# K22.net
KiCad netlist of a schematic drawn in Altium Designer
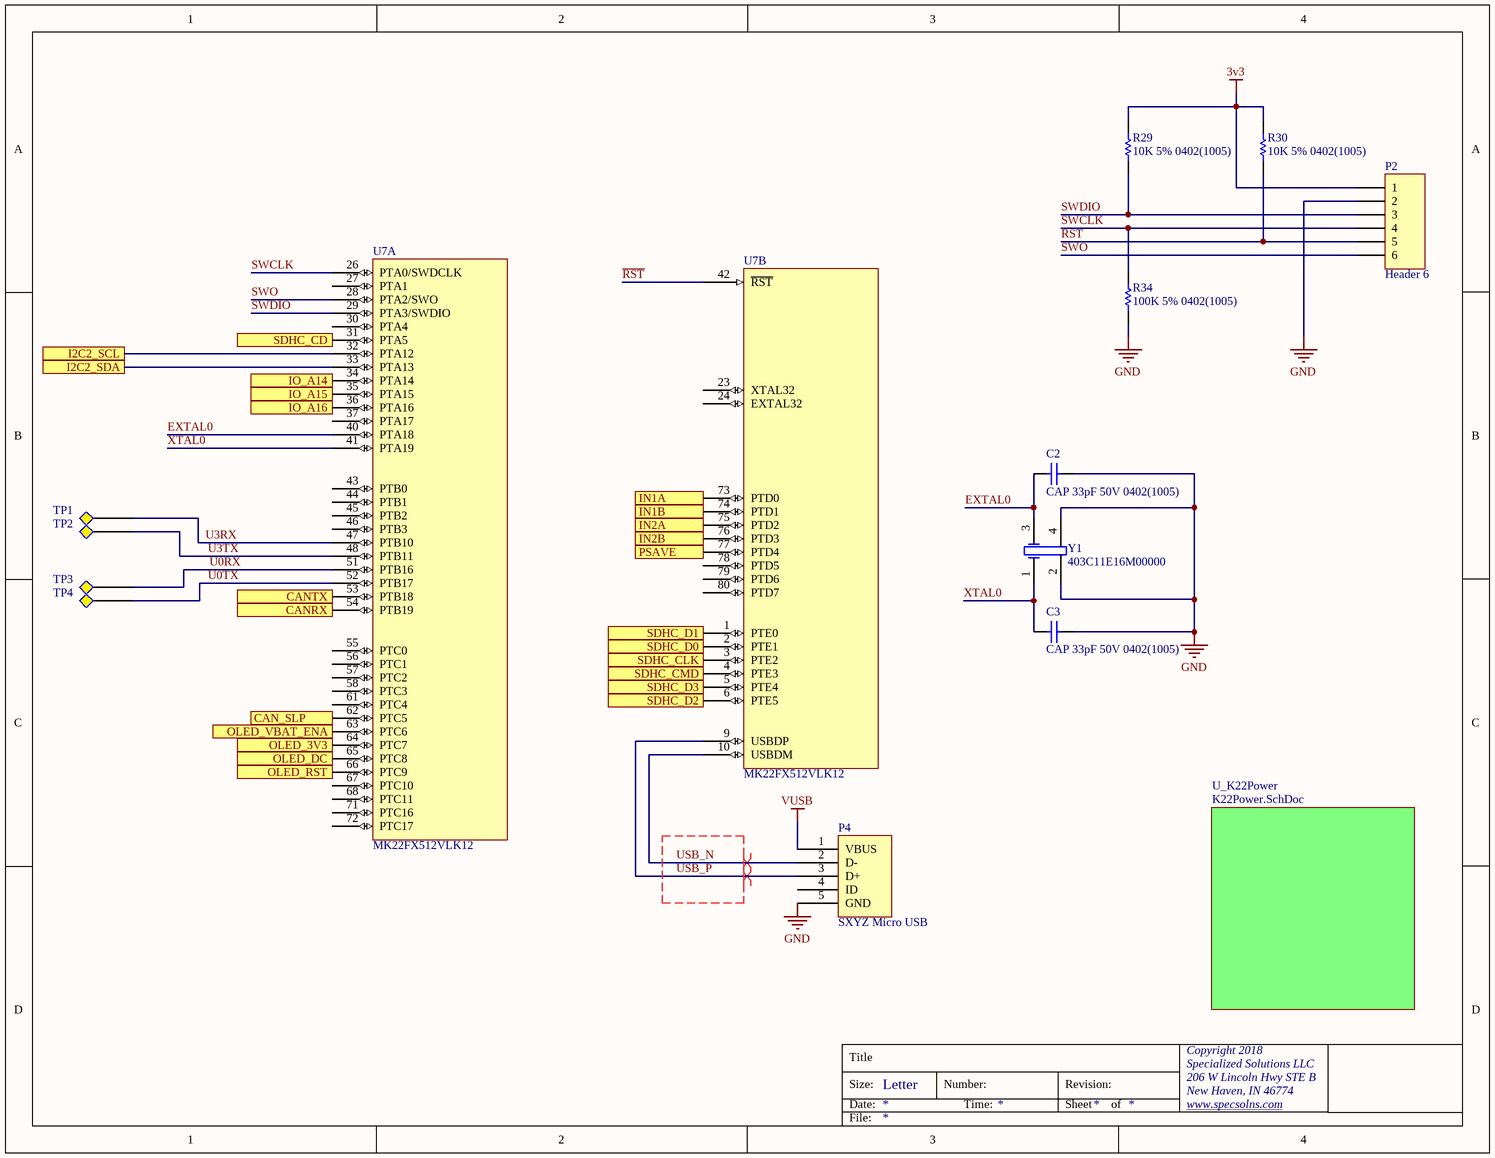
[diagram p0: K22.SchDoc]

(export (version "E")
  (design (tool "Eeschema 10.0.6"))
  (components
    (comp (ref "C2")
      (value "CAP 33pF 50V 0402(1005)")
      (footprint "CAPC0402(1005)60_N")
      (description "CAP 33pF 50V ±5% 0402 (1005 Metric) Thickness 0.6mm SMD")
      (fields (field (name "TOLERANCE") "Â±5%"))
      (libsource (lib "Altium Content Vault") (part "CAP"))
    )
    (comp (ref "C3")
      (value "CAP 33pF 50V 0402(1005)")
      (footprint "CAPC0402(1005)60_N")
      (description "CAP 33pF 50V ±5% 0402 (1005 Metric) Thickness 0.6mm SMD")
      (fields (field (name "TOLERANCE") "Â±5%"))
      (libsource (lib "Altium Content Vault") (part "CAP"))
    )
    (comp (ref "P2")
      (value "Header 6")
      (footprint "Parts:HDR1X6")
      (description "Header, 6-Pin")
      (fields (field (name "PUBLISHER") "Altium Limited"))
      (libsource (lib "Miscellaneous Connectors") (part "Header 6"))
    )
    (comp (ref "P4")
      (value "SXYZ Micro USB")
      (footprint "SXYZ Micro USB")
      (description "Micro USB Connector")
      (libsource (lib "Parts") (part "SXYZ MicroUSB"))
    )
    (comp (ref "R29")
      (value "10K 5% 0402(1005)")
      (footprint "RESC0402(1005)_N")
      (description "10K 0.063W 5% 0402 (1005 Metric)  SMD")
      (fields (field (name "TOLERANCE") "5 %") (field (name "POWER") "0.063 W"))
      (libsource (lib "Altium Content Vault") (part "RES"))
    )
    (comp (ref "R30")
      (value "10K 5% 0402(1005)")
      (footprint "RESC0402(1005)_N")
      (description "10K 0.063W 5% 0402 (1005 Metric)  SMD")
      (fields (field (name "TOLERANCE") "5 %") (field (name "POWER") "0.063 W"))
      (libsource (lib "Altium Content Vault") (part "RES"))
    )
    (comp (ref "R34")
      (value "100K 5% 0402(1005)")
      (footprint "RESC0402(1005)_L")
      (description "100K 0.063W 5% 0402 (1005 Metric)  SMD")
      (fields (field (name "POWER") "0.063 W") (field (name "TOLERANCE") "5 %"))
      (libsource (lib "Altium Content Vault") (part "RES"))
    )
    (comp (ref "TP1") (value "Test Point") (footprint "TP") (libsource (lib "parts") (part "TP")))
    (comp (ref "TP2") (value "Test Point") (footprint "TP") (libsource (lib "parts") (part "TP")))
    (comp (ref "TP3") (value "Test Point") (footprint "TP") (libsource (lib "parts") (part "TP")))
    (comp (ref "TP4") (value "Test Point") (footprint "TP") (libsource (lib "parts") (part "TP")))
    (comp (ref "U7")
      (value "MK22FX512VLK12")
      (footprint "TSQFP50P1400X1400X160-80N")
      (libsource (lib "parts") (part "MK22FX512VLK12"))
    )
    (comp (ref "Y1")
      (value "403C11E16M00000")
      (footprint "DFN155P250X80-4N")
      (description "CRYSTAL 16.0000MHZ 20PF SMD 3.20x2.50")
      (fields (field (name "PUBLISHER") "Altium Limited"))
      (libsource (lib "parts") (part "403C11E16M00000"))
    )
  )
  (nets
    (net (code "1") (name "/CANRX") (class "Default")
      (node (ref "U7") (pin "54") (pinfunction "PTB19_54") (pintype "bidirectional"))
    )
    (net (code "2") (name "/CANTX") (class "Default")
      (node (ref "U7") (pin "53") (pinfunction "PTB18_53") (pintype "bidirectional"))
    )
    (net (code "3") (name "/CAN_SLP") (class "Default")
      (node (ref "U7") (pin "62") (pinfunction "PTC5_62") (pintype "bidirectional"))
    )
    (net (code "4") (name "/EXTAL0") (class "Default")
      (node (ref "C2") (pin "1") (pinfunction "1_1") (pintype "passive"))
      (node (ref "U7") (pin "40") (pinfunction "PTA18_40") (pintype "bidirectional"))
      (node (ref "Y1") (pin "3") (pinfunction "OSC2_3") (pintype "passive"))
    )
    (net (code "5") (name "/I2C2_SCL") (class "Default")
      (node (ref "U7") (pin "32") (pinfunction "PTA12_32") (pintype "bidirectional"))
    )
    (net (code "6") (name "/I2C2_SDA") (class "Default")
      (node (ref "U7") (pin "33") (pinfunction "PTA13_33") (pintype "bidirectional"))
    )
    (net (code "7") (name "/IN1A") (class "Default")
      (node (ref "U7") (pin "73") (pinfunction "PTD0_73") (pintype "bidirectional"))
    )
    (net (code "8") (name "/IN1B") (class "Default")
      (node (ref "U7") (pin "74") (pinfunction "PTD1_74") (pintype "bidirectional"))
    )
    (net (code "9") (name "/IN2A") (class "Default")
      (node (ref "U7") (pin "75") (pinfunction "PTD2_75") (pintype "bidirectional"))
    )
    (net (code "10") (name "/IN2B") (class "Default")
      (node (ref "U7") (pin "76") (pinfunction "PTD3_76") (pintype "bidirectional"))
    )
    (net (code "11") (name "/IO_A14") (class "Default")
      (node (ref "U7") (pin "34") (pinfunction "PTA14_34") (pintype "bidirectional"))
    )
    (net (code "12") (name "/IO_A15") (class "Default")
      (node (ref "U7") (pin "35") (pinfunction "PTA15_35") (pintype "bidirectional"))
    )
    (net (code "13") (name "/IO_A16") (class "Default")
      (node (ref "U7") (pin "36") (pinfunction "PTA16_36") (pintype "bidirectional"))
    )
    (net (code "14") (name "/OLED_3V3") (class "Default")
      (node (ref "U7") (pin "64") (pinfunction "PTC7_64") (pintype "bidirectional"))
    )
    (net (code "15") (name "/OLED_DC") (class "Default")
      (node (ref "U7") (pin "65") (pinfunction "PTC8_65") (pintype "bidirectional"))
    )
    (net (code "16") (name "/OLED_RST") (class "Default")
      (node (ref "U7") (pin "66") (pinfunction "PTC9_66") (pintype "bidirectional"))
    )
    (net (code "17") (name "/OLED_VBAT_ENA") (class "Default")
      (node (ref "U7") (pin "63") (pinfunction "PTC6_63") (pintype "bidirectional"))
    )
    (net (code "18") (name "/PSAVE") (class "Default")
      (node (ref "U7") (pin "77") (pinfunction "PTD4_77") (pintype "bidirectional"))
    )
    (net (code "19") (name "/RST") (class "Default")
      (node (ref "P2") (pin "5") (pinfunction "5_5") (pintype "passive"))
      (node (ref "R30") (pin "1") (pinfunction "1_1") (pintype "passive"))
      (node (ref "U7") (pin "42") (pinfunction "RST_42") (pintype "input"))
    )
    (net (code "20") (name "/SDHC_CD") (class "Default")
      (node (ref "U7") (pin "31") (pinfunction "PTA5_31") (pintype "bidirectional"))
    )
    (net (code "21") (name "/SDHC_CLK") (class "Default")
      (node (ref "U7") (pin "3") (pinfunction "PTE2_3") (pintype "bidirectional"))
    )
    (net (code "22") (name "/SDHC_CMD") (class "Default")
      (node (ref "U7") (pin "4") (pinfunction "PTE3_4") (pintype "bidirectional"))
    )
    (net (code "23") (name "/SDHC_D0") (class "Default")
      (node (ref "U7") (pin "2") (pinfunction "PTE1_2") (pintype "bidirectional"))
    )
    (net (code "24") (name "/SDHC_D1") (class "Default")
      (node (ref "U7") (pin "1") (pinfunction "PTE0_1") (pintype "bidirectional"))
    )
    (net (code "25") (name "/SDHC_D2") (class "Default")
      (node (ref "U7") (pin "6") (pinfunction "PTE5_6") (pintype "bidirectional"))
    )
    (net (code "26") (name "/SDHC_D3") (class "Default")
      (node (ref "U7") (pin "5") (pinfunction "PTE4_5") (pintype "bidirectional"))
    )
    (net (code "27") (name "/SWCLK") (class "Default")
      (node (ref "P2") (pin "4") (pinfunction "4_4") (pintype "passive"))
      (node (ref "R34") (pin "2") (pinfunction "2_2") (pintype "passive"))
      (node (ref "U7") (pin "26") (pinfunction "PTA0/SWDCLK_26") (pintype "bidirectional"))
    )
    (net (code "28") (name "/SWDIO") (class "Default")
      (node (ref "P2") (pin "3") (pinfunction "3_3") (pintype "passive"))
      (node (ref "R29") (pin "1") (pinfunction "1_1") (pintype "passive"))
      (node (ref "U7") (pin "29") (pinfunction "PTA3/SWDIO_29") (pintype "bidirectional"))
    )
    (net (code "29") (name "/SWO") (class "Default")
      (node (ref "P2") (pin "6") (pinfunction "6_6") (pintype "passive"))
      (node (ref "U7") (pin "28") (pinfunction "PTA2/SWO_28") (pintype "bidirectional"))
    )
    (net (code "30") (name "/U0RX") (class "Default")
      (node (ref "TP3") (pin "1") (pinfunction "1_1") (pintype "passive"))
      (node (ref "U7") (pin "51") (pinfunction "PTB16_51") (pintype "bidirectional"))
    )
    (net (code "31") (name "/U0TX") (class "Default")
      (node (ref "TP4") (pin "1") (pinfunction "1_1") (pintype "passive"))
      (node (ref "U7") (pin "52") (pinfunction "PTB17_52") (pintype "bidirectional"))
    )
    (net (code "32") (name "/U3RX") (class "Default")
      (node (ref "TP1") (pin "1") (pinfunction "1_1") (pintype "passive"))
      (node (ref "U7") (pin "47") (pinfunction "PTB10_47") (pintype "bidirectional"))
    )
    (net (code "33") (name "/U3TX") (class "Default")
      (node (ref "TP2") (pin "1") (pinfunction "1_1") (pintype "passive"))
      (node (ref "U7") (pin "48") (pinfunction "PTB11_48") (pintype "bidirectional"))
    )
    (net (code "34") (name "/USB_N") (class "Default")
      (node (ref "P4") (pin "2") (pinfunction "D-_2") (pintype "passive"))
      (node (ref "U7") (pin "10") (pinfunction "USBDM_10") (pintype "bidirectional"))
    )
    (net (code "35") (name "/USB_P") (class "Default")
      (node (ref "P4") (pin "3") (pinfunction "D+_3") (pintype "passive"))
      (node (ref "U7") (pin "9") (pinfunction "USBDP_9") (pintype "bidirectional"))
    )
    (net (code "36") (name "/XTAL0") (class "Default")
      (node (ref "C3") (pin "1") (pinfunction "1_1") (pintype "passive"))
      (node (ref "U7") (pin "41") (pinfunction "PTA19_41") (pintype "bidirectional"))
      (node (ref "Y1") (pin "1") (pinfunction "OSC1_1") (pintype "passive"))
    )
    (net (code "37") (name "3v3") (class "Default")
      (node (ref "P2") (pin "1") (pinfunction "1_1") (pintype "passive"))
      (node (ref "R29") (pin "2") (pinfunction "2_2") (pintype "passive"))
      (node (ref "R30") (pin "2") (pinfunction "2_2") (pintype "passive"))
    )
    (net (code "38") (name "GND") (class "Default")
      (node (ref "C2") (pin "2") (pinfunction "2_2") (pintype "passive"))
      (node (ref "C3") (pin "2") (pinfunction "2_2") (pintype "passive"))
      (node (ref "P2") (pin "2") (pinfunction "2_2") (pintype "passive"))
      (node (ref "P4") (pin "5") (pinfunction "GND_5") (pintype "passive"))
      (node (ref "R34") (pin "1") (pinfunction "1_1") (pintype "passive"))
      (node (ref "Y1") (pin "2") (pinfunction "GND_2") (pintype "passive"))
      (node (ref "Y1") (pin "4") (pinfunction "GND_4") (pintype "passive"))
    )
    (net (code "39") (name "VUSB") (class "Default")
      (node (ref "P4") (pin "1") (pinfunction "VBUS_1") (pintype "passive"))
    )
    (net (code "40") (name "unconnected-(P4-ID-Pad4)") (class "Default")
      (node (ref "P4") (pin "4") (pinfunction "ID_4") (pintype "passive"))
    )
    (net (code "41") (name "unconnected-(U7A-PTA1-Pad27)") (class "Default")
      (node (ref "U7") (pin "27") (pinfunction "PTA1_27") (pintype "bidirectional"))
    )
    (net (code "42") (name "unconnected-(U7A-PTA4-Pad30)") (class "Default")
      (node (ref "U7") (pin "30") (pinfunction "PTA4_30") (pintype "bidirectional"))
    )
    (net (code "43") (name "unconnected-(U7A-PTA17-Pad37)") (class "Default")
      (node (ref "U7") (pin "37") (pinfunction "PTA17_37") (pintype "bidirectional"))
    )
    (net (code "44") (name "unconnected-(U7A-PTB0-Pad43)") (class "Default")
      (node (ref "U7") (pin "43") (pinfunction "PTB0_43") (pintype "bidirectional"))
    )
    (net (code "45") (name "unconnected-(U7A-PTB1-Pad44)") (class "Default")
      (node (ref "U7") (pin "44") (pinfunction "PTB1_44") (pintype "bidirectional"))
    )
    (net (code "46") (name "unconnected-(U7A-PTB2-Pad45)") (class "Default")
      (node (ref "U7") (pin "45") (pinfunction "PTB2_45") (pintype "bidirectional"))
    )
    (net (code "47") (name "unconnected-(U7A-PTB3-Pad46)") (class "Default")
      (node (ref "U7") (pin "46") (pinfunction "PTB3_46") (pintype "bidirectional"))
    )
    (net (code "48") (name "unconnected-(U7A-PTC0-Pad55)") (class "Default")
      (node (ref "U7") (pin "55") (pinfunction "PTC0_55") (pintype "bidirectional"))
    )
    (net (code "49") (name "unconnected-(U7A-PTC1-Pad56)") (class "Default")
      (node (ref "U7") (pin "56") (pinfunction "PTC1_56") (pintype "bidirectional"))
    )
    (net (code "50") (name "unconnected-(U7A-PTC2-Pad57)") (class "Default")
      (node (ref "U7") (pin "57") (pinfunction "PTC2_57") (pintype "bidirectional"))
    )
    (net (code "51") (name "unconnected-(U7A-PTC3-Pad58)") (class "Default")
      (node (ref "U7") (pin "58") (pinfunction "PTC3_58") (pintype "bidirectional"))
    )
    (net (code "52") (name "unconnected-(U7A-PTC4-Pad61)") (class "Default")
      (node (ref "U7") (pin "61") (pinfunction "PTC4_61") (pintype "bidirectional"))
    )
    (net (code "53") (name "unconnected-(U7A-PTC10-Pad67)") (class "Default")
      (node (ref "U7") (pin "67") (pinfunction "PTC10_67") (pintype "bidirectional"))
    )
    (net (code "54") (name "unconnected-(U7A-PTC11-Pad68)") (class "Default")
      (node (ref "U7") (pin "68") (pinfunction "PTC11_68") (pintype "bidirectional"))
    )
    (net (code "55") (name "unconnected-(U7A-PTC16-Pad71)") (class "Default")
      (node (ref "U7") (pin "71") (pinfunction "PTC16_71") (pintype "bidirectional"))
    )
    (net (code "56") (name "unconnected-(U7A-PTC17-Pad72)") (class "Default")
      (node (ref "U7") (pin "72") (pinfunction "PTC17_72") (pintype "bidirectional"))
    )
    (net (code "57") (name "unconnected-(U7B-EXTAL32-Pad24)") (class "Default")
      (node (ref "U7") (pin "24") (pinfunction "EXTAL32_24") (pintype "bidirectional"))
    )
    (net (code "58") (name "unconnected-(U7B-PTD5-Pad78)") (class "Default")
      (node (ref "U7") (pin "78") (pinfunction "PTD5_78") (pintype "bidirectional"))
    )
    (net (code "59") (name "unconnected-(U7B-PTD6-Pad79)") (class "Default")
      (node (ref "U7") (pin "79") (pinfunction "PTD6_79") (pintype "bidirectional"))
    )
    (net (code "60") (name "unconnected-(U7B-PTD7-Pad80)") (class "Default")
      (node (ref "U7") (pin "80") (pinfunction "PTD7_80") (pintype "bidirectional"))
    )
    (net (code "61") (name "unconnected-(U7B-XTAL32-Pad23)") (class "Default")
      (node (ref "U7") (pin "23") (pinfunction "XTAL32_23") (pintype "bidirectional"))
    )
  )
)
